# Gain.net
KiCad netlist of a schematic drawn in Altium Designer
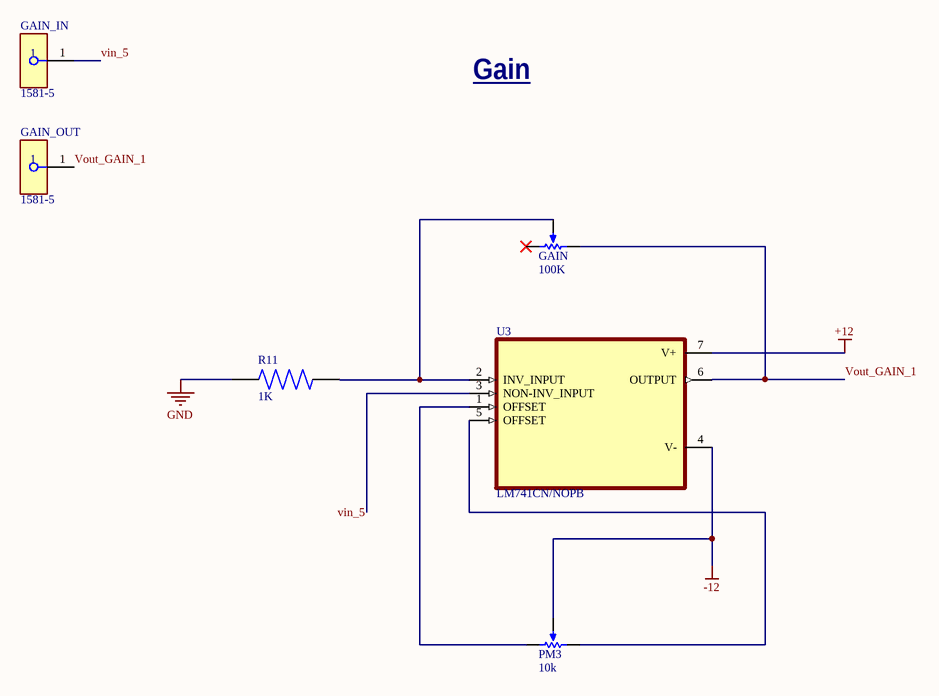
[diagram p0: Gain.SchDoc]

(export (version "E")
  (design (tool "Eeschema 10.0.6"))
  (components
    (comp (ref "GAIN")
      (value "100K")
      (footprint "BOUR-3852A-282-103AL-3_V")
      (description "Diameter Panel Control, 10 KOhm, +/- 10%, 2 W, -1 to 125 degC, 3-Pin THD, RoHS, Bulk")
      (fields (field (name "TOLERANCE") "±10%") (field (name "MANUFACTURER") "Bourns"))
      (libsource (lib "Altium Content Vault") (part "RES-POT-3"))
    )
    (comp (ref "GAIN_IN")
      (value "1581-5")
      (footprint "FP-1581-5-MFG")
      (description "CONN BANANA JACK TURRET GREEN")
      (libsource (lib "Altium Content Vault") (part "c5c826e0c4b67fe3b42ef77f2d4decc"))
    )
    (comp (ref "GAIN_OUT")
      (value "1581-5")
      (footprint "FP-1581-5-MFG")
      (description "CONN BANANA JACK TURRET GREEN")
      (libsource (lib "Altium Content Vault") (part "c5c826e0c4b67fe3b42ef77f2d4decc"))
    )
    (comp (ref "PM3")
      (value "10k")
      (footprint "BOUR-3362P")
      (description "Square Trimpot(R) Trimming Potentiometer, 10 KOhm, 300 V, -55 to 125 degC, 3-Pin THD, RoHS, Tube")
      (fields (field (name "TOLERANCE") "1%"))
      (libsource (lib "Altium Content Vault") (part "RES-POT-3"))
    )
    (comp (ref "R11")
      (value "1K")
      (footprint "RESAD1100W55L680D260")
      (description "1.07 kOhms Â±1% 0.25W, 1/4W Through Hole Resistor Axial - Metal Film")
      (fields (field (name "MF") "Yageo") (field (name "MP") "MFR-25FBF52-1K"))
      (libsource (lib "MFR-25FBF52-1K") (part "MFR-25FBF52-1K"))
    )
    (comp (ref "U3")
      (value "LM741CN/NOPB")
      (footprint "DIP794W45P254L959H508Q8")
      (description "Single, 44-V, 1-MHz operational amplifier")
      (fields (field (name "MF") "Texas Instruments"))
      (libsource (lib "LM741CN_NOPB (1)") (part "LM741CN/NOPB"))
    )
  )
  (nets
    (net (code "1") (name "+12") (class "Default")
      (node (ref "U3") (pin "7") (pinfunction "V+_7") (pintype "power_in"))
    )
    (net (code "2") (name "-12") (class "Default")
      (node (ref "PM3") (pin "2") (pinfunction "S_2") (pintype "passive"))
      (node (ref "U3") (pin "4") (pinfunction "V-_4") (pintype "power_in"))
    )
    (net (code "3") (name "/Vout_GAIN_1") (class "Default")
      (node (ref "GAIN") (pin "1") (pinfunction "CCW_1") (pintype "passive"))
      (node (ref "GAIN_OUT") (pin "1") (pinfunction "1_1") (pintype "passive"))
      (node (ref "U3") (pin "6") (pinfunction "OUTPUT_6") (pintype "output"))
    )
    (net (code "4") (name "/vin_5") (class "Default")
      (node (ref "GAIN_IN") (pin "1") (pinfunction "1_1") (pintype "passive"))
      (node (ref "U3") (pin "3") (pinfunction "NON-INV_INPUT_3") (pintype "input"))
    )
    (net (code "5") (name "GND") (class "Default")
      (node (ref "R11") (pin "1") (pinfunction "1_1") (pintype "passive"))
    )
    (net (code "6") (name "Net-(GAIN-S)") (class "Default")
      (node (ref "GAIN") (pin "2") (pinfunction "S_2") (pintype "passive"))
      (node (ref "R11") (pin "2") (pinfunction "2_2") (pintype "passive"))
      (node (ref "U3") (pin "2") (pinfunction "INV_INPUT_2") (pintype "input"))
    )
    (net (code "7") (name "Net-(PM3-CCW)") (class "Default")
      (node (ref "PM3") (pin "1") (pinfunction "CCW_1") (pintype "passive"))
      (node (ref "U3") (pin "5") (pinfunction "OFFSET_5") (pintype "input"))
    )
    (net (code "8") (name "Net-(PM3-CW)") (class "Default")
      (node (ref "PM3") (pin "3") (pinfunction "CW_3") (pintype "passive"))
      (node (ref "U3") (pin "1") (pinfunction "OFFSET_1") (pintype "input"))
    )
    (net (code "9") (name "unconnected-(GAIN-CW-Pad3)") (class "Default")
      (node (ref "GAIN") (pin "3") (pinfunction "CW_3") (pintype "passive+no_connect"))
    )
  )
)
